# I2C_Mini_Line_Sensor.net
KiCad netlist of a schematic drawn in EAGLE
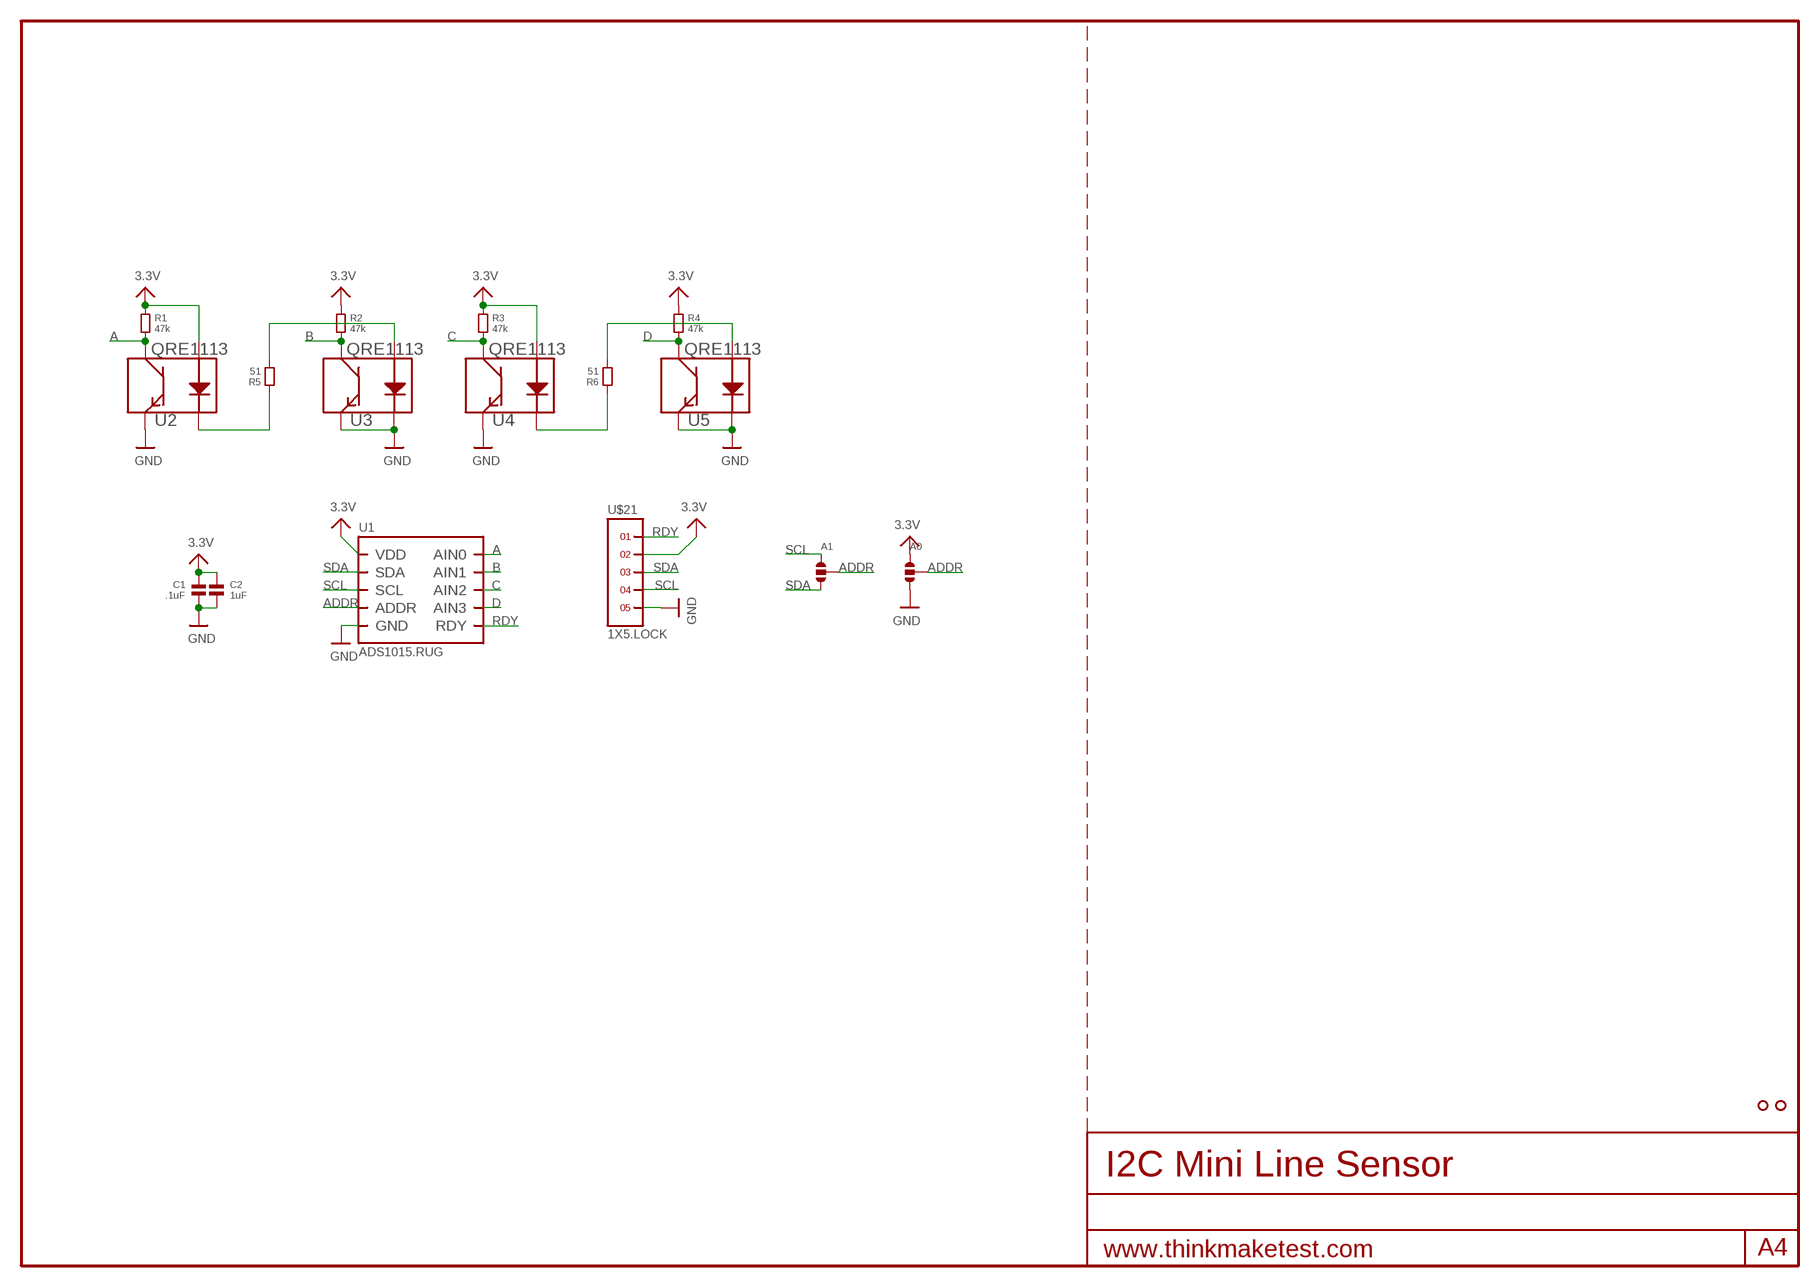
[diagram p0: schematic, sheet 1]

(export (version "E")
  (design (tool "Eeschema 10.0.6"))
  (components
    (comp (ref "A0")
      (value "SOLDERJUMPER.3.MED")
      (footprint "eagle-import:3.MED")
      (libsource (lib "eagle-import") (part "SOLDERJUMPER.3.MED"))
    )
    (comp (ref "A1")
      (value "SOLDERJUMPER.3.MED")
      (footprint "eagle-import:3.MED")
      (libsource (lib "eagle-import") (part "SOLDERJUMPER.3.MED"))
    )
    (comp (ref "C1")
      (value ".1uF")
      (footprint "eagle-import:0603")
      (libsource (lib "eagle-import") (part "CAPACITOR.0603"))
    )
    (comp (ref "C2")
      (value "1uF")
      (footprint "eagle-import:0603")
      (libsource (lib "eagle-import") (part "CAPACITOR.0603"))
    )
    (comp (ref "R1")
      (value "47k")
      (footprint "eagle-import:0603")
      (libsource (lib "eagle-import") (part "RESISTOR.0603"))
    )
    (comp (ref "R2")
      (value "47k")
      (footprint "eagle-import:0603")
      (libsource (lib "eagle-import") (part "RESISTOR.0603"))
    )
    (comp (ref "R3")
      (value "47k")
      (footprint "eagle-import:0603")
      (libsource (lib "eagle-import") (part "RESISTOR.0603"))
    )
    (comp (ref "R4")
      (value "47k")
      (footprint "eagle-import:0603")
      (libsource (lib "eagle-import") (part "RESISTOR.0603"))
    )
    (comp (ref "R5")
      (value "51")
      (footprint "eagle-import:0603")
      (libsource (lib "eagle-import") (part "RESISTOR.0603"))
    )
    (comp (ref "R6")
      (value "51")
      (footprint "eagle-import:0603")
      (libsource (lib "eagle-import") (part "RESISTOR.0603"))
    )
    (comp (ref "U$3")
      (value "HOLE.2MM")
      (footprint "eagle-import:2MM")
      (libsource (lib "eagle-import") (part "HOLE.2MM"))
    )
    (comp (ref "U$18")
      (value "HOLE.2MM")
      (footprint "eagle-import:2MM")
      (libsource (lib "eagle-import") (part "HOLE.2MM"))
    )
    (comp (ref "U$21")
      (value "1X5.LOCK")
      (footprint "eagle-import:1X5.LOCK")
      (libsource (lib "eagle-import") (part "1X5.LOCK"))
    )
    (comp (ref "U1")
      (value "ADS1015.RUG")
      (footprint "eagle-import:RUG.10")
      (libsource (lib "eagle-import") (part "ADS1015.RUG"))
    )
    (comp (ref "U2")
      (value "QRE1113")
      (footprint "eagle-import:QRE1113")
      (libsource (lib "eagle-import") (part "QRE1113"))
    )
    (comp (ref "U3")
      (value "QRE1113")
      (footprint "eagle-import:QRE1113")
      (libsource (lib "eagle-import") (part "QRE1113"))
    )
    (comp (ref "U4")
      (value "QRE1113")
      (footprint "eagle-import:QRE1113")
      (libsource (lib "eagle-import") (part "QRE1113"))
    )
    (comp (ref "U5")
      (value "QRE1113")
      (footprint "eagle-import:QRE1113")
      (libsource (lib "eagle-import") (part "QRE1113"))
    )
  )
  (nets
    (net (code "1") (name "/A") (class "Default")
      (node (ref "R1") (pin "2") (pinfunction "2_2") (pintype "bidirectional"))
      (node (ref "U1") (pin "4") (pinfunction "AIN0_4") (pintype "bidirectional"))
      (node (ref "U2") (pin "3") (pinfunction "C_3") (pintype "bidirectional"))
    )
    (net (code "2") (name "/ADDR") (class "Default")
      (node (ref "A0") (pin "2") (pinfunction "2_2") (pintype "bidirectional"))
      (node (ref "A1") (pin "2") (pinfunction "2_2") (pintype "bidirectional"))
      (node (ref "U1") (pin "1") (pinfunction "ADDR_1") (pintype "bidirectional"))
    )
    (net (code "3") (name "/B") (class "Default")
      (node (ref "R2") (pin "2") (pinfunction "2_2") (pintype "bidirectional"))
      (node (ref "U1") (pin "5") (pinfunction "AIN1_5") (pintype "bidirectional"))
      (node (ref "U3") (pin "3") (pinfunction "C_3") (pintype "bidirectional"))
    )
    (net (code "4") (name "/C") (class "Default")
      (node (ref "R3") (pin "2") (pinfunction "2_2") (pintype "bidirectional"))
      (node (ref "U1") (pin "6") (pinfunction "AIN2_6") (pintype "bidirectional"))
      (node (ref "U4") (pin "3") (pinfunction "C_3") (pintype "bidirectional"))
    )
    (net (code "5") (name "/D") (class "Default")
      (node (ref "R4") (pin "2") (pinfunction "2_2") (pintype "bidirectional"))
      (node (ref "U1") (pin "7") (pinfunction "AIN3_7") (pintype "bidirectional"))
      (node (ref "U5") (pin "3") (pinfunction "C_3") (pintype "bidirectional"))
    )
    (net (code "6") (name "/RDY") (class "Default")
      (node (ref "U$21") (pin "1") (pinfunction "1_1") (pintype "bidirectional"))
      (node (ref "U1") (pin "2") (pinfunction "RDY_2") (pintype "bidirectional"))
    )
    (net (code "7") (name "/SCL") (class "Default")
      (node (ref "A1") (pin "1") (pinfunction "1_1") (pintype "bidirectional"))
      (node (ref "U$21") (pin "4") (pinfunction "4_4") (pintype "bidirectional"))
      (node (ref "U1") (pin "10") (pinfunction "SCL_10") (pintype "bidirectional"))
    )
    (net (code "8") (name "/SDA") (class "Default")
      (node (ref "A1") (pin "3") (pinfunction "3_3") (pintype "bidirectional"))
      (node (ref "U$21") (pin "3") (pinfunction "3_3") (pintype "bidirectional"))
      (node (ref "U1") (pin "9") (pinfunction "SDA_9") (pintype "bidirectional"))
    )
    (net (code "9") (name "3.3V") (class "Default")
      (node (ref "A0") (pin "1") (pinfunction "1_1") (pintype "bidirectional"))
      (node (ref "C1") (pin "1") (pinfunction "1_1") (pintype "bidirectional"))
      (node (ref "C2") (pin "1") (pinfunction "1_1") (pintype "bidirectional"))
      (node (ref "R1") (pin "1") (pinfunction "1_1") (pintype "bidirectional"))
      (node (ref "R2") (pin "1") (pinfunction "1_1") (pintype "bidirectional"))
      (node (ref "R3") (pin "1") (pinfunction "1_1") (pintype "bidirectional"))
      (node (ref "R4") (pin "1") (pinfunction "1_1") (pintype "bidirectional"))
      (node (ref "U$21") (pin "2") (pinfunction "2_2") (pintype "bidirectional"))
      (node (ref "U1") (pin "8") (pinfunction "VDD_8") (pintype "bidirectional"))
      (node (ref "U2") (pin "1") (pinfunction "A_1") (pintype "bidirectional"))
      (node (ref "U4") (pin "1") (pinfunction "A_1") (pintype "bidirectional"))
    )
    (net (code "10") (name "GND") (class "Default")
      (node (ref "A0") (pin "3") (pinfunction "3_3") (pintype "bidirectional"))
      (node (ref "C1") (pin "2") (pinfunction "2_2") (pintype "bidirectional"))
      (node (ref "C2") (pin "2") (pinfunction "2_2") (pintype "bidirectional"))
      (node (ref "U$21") (pin "5") (pinfunction "5_5") (pintype "bidirectional"))
      (node (ref "U1") (pin "3") (pinfunction "GND_3") (pintype "bidirectional"))
      (node (ref "U2") (pin "4") (pinfunction "E_4") (pintype "bidirectional"))
      (node (ref "U3") (pin "2") (pinfunction "K_2") (pintype "bidirectional"))
      (node (ref "U3") (pin "4") (pinfunction "E_4") (pintype "bidirectional"))
      (node (ref "U4") (pin "4") (pinfunction "E_4") (pintype "bidirectional"))
      (node (ref "U5") (pin "2") (pinfunction "K_2") (pintype "bidirectional"))
      (node (ref "U5") (pin "4") (pinfunction "E_4") (pintype "bidirectional"))
    )
    (net (code "11") (name "Net-(U2-K)") (class "Default")
      (node (ref "R5") (pin "1") (pinfunction "1_1") (pintype "bidirectional"))
      (node (ref "U2") (pin "2") (pinfunction "K_2") (pintype "bidirectional"))
    )
    (net (code "12") (name "Net-(U3-A)") (class "Default")
      (node (ref "R5") (pin "2") (pinfunction "2_2") (pintype "bidirectional"))
      (node (ref "U3") (pin "1") (pinfunction "A_1") (pintype "bidirectional"))
    )
    (net (code "13") (name "Net-(U4-K)") (class "Default")
      (node (ref "R6") (pin "1") (pinfunction "1_1") (pintype "bidirectional"))
      (node (ref "U4") (pin "2") (pinfunction "K_2") (pintype "bidirectional"))
    )
    (net (code "14") (name "Net-(U5-A)") (class "Default")
      (node (ref "R6") (pin "2") (pinfunction "2_2") (pintype "bidirectional"))
      (node (ref "U5") (pin "1") (pinfunction "A_1") (pintype "bidirectional"))
    )
  )
)
